# SCS.net
KiCad netlist of a schematic drawn in EAGLE
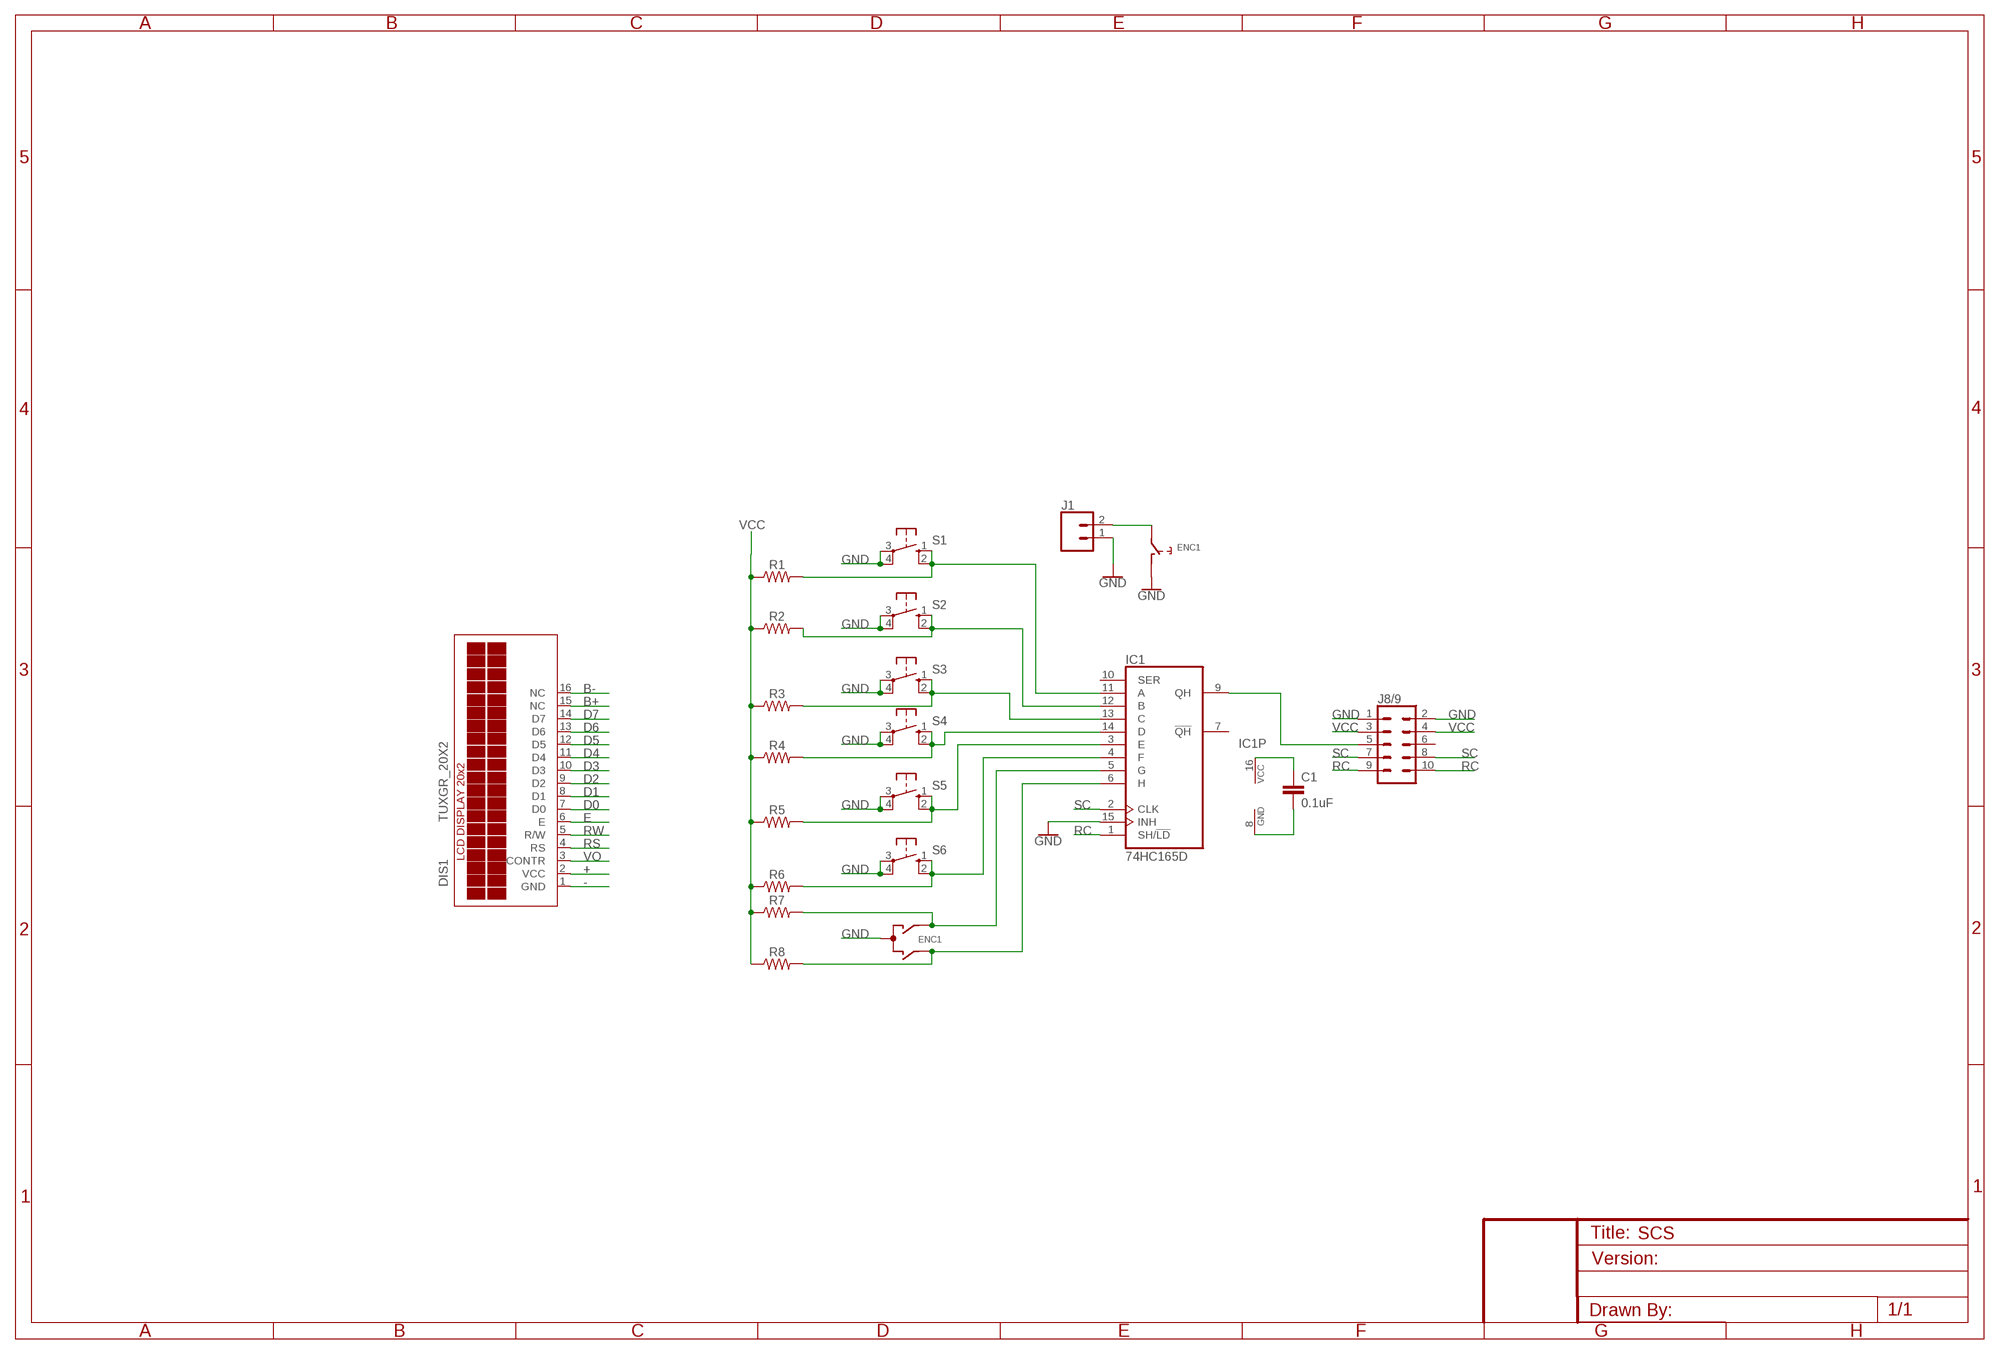
[diagram p0: schematic, sheet 1]

(export (version "E")
  (design (tool "Eeschema 10.0.6"))
  (components
    (comp (ref "C1")
      (value "0.1uF")
      (footprint "eagle-import:0603")
      (libsource (lib "eagle-import") (part "0.1UF-0603-25V-(+80/-20%)"))
    )
    (comp (ref "DIS1")
      (value "TUXGR_20X2")
      (footprint "eagle-import:TUXGR_20X2")
      (libsource (lib "eagle-import") (part "TUXGR_20X2"))
    )
    (comp (ref "ENC1")
      (value "EC12E_SW")
      (footprint "eagle-import:ALPS_EC12E_SW")
      (fields (field (name "MPN") "EC12E2424407"))
      (libsource (lib "eagle-import") (part "EC12E_SW"))
    )
    (comp (ref "IC1")
      (value "74HC165D")
      (footprint "eagle-import:SO16")
      (libsource (lib "eagle-import") (part "74165DHC"))
    )
    (comp (ref "J1")
      (value "CONN_02")
      (footprint "eagle-import:1X02")
      (libsource (lib "eagle-import") (part "CONN_02"))
    )
    (comp (ref "J8/9")
      (value "CONN_05X2SHD_LOCK")
      (footprint "eagle-import:2X5-SHROUDED_LOCK")
      (libsource (lib "eagle-import") (part "CONN_05X2SHD_LOCK"))
    )
    (comp (ref "R1")
      (value "10k")
      (footprint "eagle-import:0603")
      (libsource (lib "eagle-import") (part "10KOHM-0603-1/10W-1%"))
    )
    (comp (ref "R2")
      (value "10k")
      (footprint "eagle-import:0603")
      (libsource (lib "eagle-import") (part "10KOHM-0603-1/10W-1%"))
    )
    (comp (ref "R3")
      (value "10k")
      (footprint "eagle-import:0603")
      (libsource (lib "eagle-import") (part "10KOHM-0603-1/10W-1%"))
    )
    (comp (ref "R4")
      (value "10k")
      (footprint "eagle-import:0603")
      (libsource (lib "eagle-import") (part "10KOHM-0603-1/10W-1%"))
    )
    (comp (ref "R5")
      (value "10k")
      (footprint "eagle-import:0603")
      (libsource (lib "eagle-import") (part "10KOHM-0603-1/10W-1%"))
    )
    (comp (ref "R6")
      (value "10k")
      (footprint "eagle-import:0603")
      (libsource (lib "eagle-import") (part "10KOHM-0603-1/10W-1%"))
    )
    (comp (ref "R7")
      (value "10k")
      (footprint "eagle-import:0603")
      (libsource (lib "eagle-import") (part "10KOHM-0603-1/10W-1%"))
    )
    (comp (ref "R8")
      (value "10k")
      (footprint "eagle-import:0603")
      (libsource (lib "eagle-import") (part "10KOHM-0603-1/10W-1%"))
    )
    (comp (ref "S1")
      (value "40-XX")
      (footprint "eagle-import:B3F-40XX")
      (fields (field (name "MF") "OMRON COMPONENTS USA") (field (name "MPN") "B3F-4000"))
      (libsource (lib "eagle-import") (part "40-XX"))
    )
    (comp (ref "S2")
      (value "40-XX")
      (footprint "eagle-import:B3F-40XX")
      (fields (field (name "MF") "OMRON COMPONENTS USA") (field (name "MPN") "B3F-4000"))
      (libsource (lib "eagle-import") (part "40-XX"))
    )
    (comp (ref "S3")
      (value "40-XX")
      (footprint "eagle-import:B3F-40XX")
      (fields (field (name "MF") "OMRON COMPONENTS USA") (field (name "MPN") "B3F-4000"))
      (libsource (lib "eagle-import") (part "40-XX"))
    )
    (comp (ref "S4")
      (value "40-XX")
      (footprint "eagle-import:B3F-40XX")
      (fields (field (name "MF") "OMRON COMPONENTS USA") (field (name "MPN") "B3F-4000"))
      (libsource (lib "eagle-import") (part "40-XX"))
    )
    (comp (ref "S5")
      (value "40-XX")
      (footprint "eagle-import:B3F-40XX")
      (fields (field (name "MF") "OMRON COMPONENTS USA") (field (name "MPN") "B3F-4000"))
      (libsource (lib "eagle-import") (part "40-XX"))
    )
    (comp (ref "S6")
      (value "40-XX")
      (footprint "eagle-import:B3F-40XX")
      (fields (field (name "MF") "OMRON COMPONENTS USA") (field (name "MPN") "B3F-4000"))
      (libsource (lib "eagle-import") (part "40-XX"))
    )
  )
  (nets
    (net (code "1") (name "/+") (class "Default")
      (node (ref "DIS1") (pin "2") (pinfunction "VCC_2") (pintype "power_in"))
    )
    (net (code "2") (name "/-") (class "Default")
      (node (ref "DIS1") (pin "1") (pinfunction "GND_1") (pintype "power_in"))
    )
    (net (code "5") (name "/D0") (class "Default")
      (node (ref "DIS1") (pin "7") (pinfunction "D0_7") (pintype "input"))
    )
    (net (code "6") (name "/D1") (class "Default")
      (node (ref "DIS1") (pin "8") (pinfunction "D1_8") (pintype "input"))
    )
    (net (code "7") (name "/D2") (class "Default")
      (node (ref "DIS1") (pin "9") (pinfunction "D2_9") (pintype "input"))
    )
    (net (code "8") (name "/D3") (class "Default")
      (node (ref "DIS1") (pin "10") (pinfunction "D3_10") (pintype "input"))
    )
    (net (code "9") (name "/D4") (class "Default")
      (node (ref "DIS1") (pin "11") (pinfunction "D4_11") (pintype "input"))
    )
    (net (code "10") (name "/D5") (class "Default")
      (node (ref "DIS1") (pin "12") (pinfunction "D5_12") (pintype "input"))
    )
    (net (code "11") (name "/D6") (class "Default")
      (node (ref "DIS1") (pin "13") (pinfunction "D6_13") (pintype "input"))
    )
    (net (code "12") (name "/D7") (class "Default")
      (node (ref "DIS1") (pin "14") (pinfunction "D7_14") (pintype "input"))
    )
    (net (code "13") (name "/E") (class "Default")
      (node (ref "DIS1") (pin "6") (pinfunction "E_6") (pintype "input"))
    )
    (net (code "14") (name "/RC") (class "Default")
      (node (ref "IC1") (pin "1") (pinfunction "SH/~{LD}_1") (pintype "input"))
      (node (ref "J8/9") (pin "10") (pinfunction "10_10") (pintype "passive"))
      (node (ref "J8/9") (pin "9") (pinfunction "9_9") (pintype "passive"))
    )
    (net (code "15") (name "/RS") (class "Default")
      (node (ref "DIS1") (pin "4") (pinfunction "RS_4") (pintype "input"))
    )
    (net (code "16") (name "/RW") (class "Default")
      (node (ref "DIS1") (pin "5") (pinfunction "R/W_5") (pintype "input"))
    )
    (net (code "17") (name "/SC") (class "Default")
      (node (ref "IC1") (pin "2") (pinfunction "CLK_2") (pintype "input"))
      (node (ref "J8/9") (pin "7") (pinfunction "7_7") (pintype "passive"))
      (node (ref "J8/9") (pin "8") (pinfunction "8_8") (pintype "passive"))
    )
    (net (code "18") (name "/VCC") (class "Default")
      (node (ref "J8/9") (pin "3") (pinfunction "3_3") (pintype "passive"))
      (node (ref "J8/9") (pin "4") (pinfunction "4_4") (pintype "passive"))
      (node (ref "R1") (pin "1") (pinfunction "1_1") (pintype "passive"))
      (node (ref "R2") (pin "1") (pinfunction "1_1") (pintype "passive"))
      (node (ref "R3") (pin "1") (pinfunction "1_1") (pintype "passive"))
      (node (ref "R4") (pin "1") (pinfunction "1_1") (pintype "passive"))
      (node (ref "R5") (pin "1") (pinfunction "1_1") (pintype "passive"))
      (node (ref "R6") (pin "1") (pinfunction "1_1") (pintype "passive"))
      (node (ref "R7") (pin "1") (pinfunction "1_1") (pintype "passive"))
      (node (ref "R8") (pin "1") (pinfunction "1_1") (pintype "passive"))
    )
    (net (code "19") (name "/VO") (class "Default")
      (node (ref "DIS1") (pin "3") (pinfunction "CONTR_3") (pintype "input"))
    )
    (net (code "20") (name "GND") (class "Default")
      (node (ref "ENC1") (pin "C") (pinfunction "C_C") (pintype "passive"))
      (node (ref "ENC1") (pin "D") (pinfunction "1_D") (pintype "passive"))
      (node (ref "IC1") (pin "15") (pinfunction "INH_15") (pintype "input"))
      (node (ref "J1") (pin "1") (pinfunction "1_1") (pintype "passive"))
      (node (ref "J8/9") (pin "1") (pinfunction "1_1") (pintype "passive"))
      (node (ref "J8/9") (pin "2") (pinfunction "2_2") (pintype "passive"))
      (node (ref "S1") (pin "3") (pinfunction "P_3") (pintype "passive"))
      (node (ref "S1") (pin "4") (pinfunction "P1_4") (pintype "passive"))
      (node (ref "S2") (pin "3") (pinfunction "P_3") (pintype "passive"))
      (node (ref "S2") (pin "4") (pinfunction "P1_4") (pintype "passive"))
      (node (ref "S3") (pin "3") (pinfunction "P_3") (pintype "passive"))
      (node (ref "S3") (pin "4") (pinfunction "P1_4") (pintype "passive"))
      (node (ref "S4") (pin "3") (pinfunction "P_3") (pintype "passive"))
      (node (ref "S4") (pin "4") (pinfunction "P1_4") (pintype "passive"))
      (node (ref "S5") (pin "3") (pinfunction "P_3") (pintype "passive"))
      (node (ref "S5") (pin "4") (pinfunction "P1_4") (pintype "passive"))
      (node (ref "S6") (pin "3") (pinfunction "P_3") (pintype "passive"))
      (node (ref "S6") (pin "4") (pinfunction "P1_4") (pintype "passive"))
    )
    (net (code "21") (name "Net-(ENC1B-2)") (class "Default")
      (node (ref "ENC1") (pin "E") (pinfunction "2_E") (pintype "passive"))
      (node (ref "J1") (pin "2") (pinfunction "2_2") (pintype "passive"))
    )
    (net (code "22") (name "Net-(IC1A-A)") (class "Default")
      (node (ref "IC1") (pin "11") (pinfunction "A_11") (pintype "input"))
      (node (ref "R1") (pin "2") (pinfunction "2_2") (pintype "passive"))
      (node (ref "S1") (pin "1") (pinfunction "S_1") (pintype "passive"))
      (node (ref "S1") (pin "2") (pinfunction "S1_2") (pintype "passive"))
    )
    (net (code "23") (name "Net-(IC1A-B)") (class "Default")
      (node (ref "IC1") (pin "12") (pinfunction "B_12") (pintype "input"))
      (node (ref "R2") (pin "2") (pinfunction "2_2") (pintype "passive"))
      (node (ref "S2") (pin "1") (pinfunction "S_1") (pintype "passive"))
      (node (ref "S2") (pin "2") (pinfunction "S1_2") (pintype "passive"))
    )
    (net (code "24") (name "Net-(IC1A-C)") (class "Default")
      (node (ref "IC1") (pin "13") (pinfunction "C_13") (pintype "input"))
      (node (ref "R3") (pin "2") (pinfunction "2_2") (pintype "passive"))
      (node (ref "S3") (pin "1") (pinfunction "S_1") (pintype "passive"))
      (node (ref "S3") (pin "2") (pinfunction "S1_2") (pintype "passive"))
    )
    (net (code "25") (name "Net-(IC1A-D)") (class "Default")
      (node (ref "IC1") (pin "14") (pinfunction "D_14") (pintype "input"))
      (node (ref "R4") (pin "2") (pinfunction "2_2") (pintype "passive"))
      (node (ref "S4") (pin "1") (pinfunction "S_1") (pintype "passive"))
      (node (ref "S4") (pin "2") (pinfunction "S1_2") (pintype "passive"))
    )
    (net (code "26") (name "Net-(IC1A-E)") (class "Default")
      (node (ref "IC1") (pin "3") (pinfunction "E_3") (pintype "input"))
      (node (ref "R5") (pin "2") (pinfunction "2_2") (pintype "passive"))
      (node (ref "S5") (pin "1") (pinfunction "S_1") (pintype "passive"))
      (node (ref "S5") (pin "2") (pinfunction "S1_2") (pintype "passive"))
    )
    (net (code "27") (name "Net-(IC1A-F)") (class "Default")
      (node (ref "IC1") (pin "4") (pinfunction "F_4") (pintype "input"))
      (node (ref "R6") (pin "2") (pinfunction "2_2") (pintype "passive"))
      (node (ref "S6") (pin "1") (pinfunction "S_1") (pintype "passive"))
      (node (ref "S6") (pin "2") (pinfunction "S1_2") (pintype "passive"))
    )
    (net (code "28") (name "Net-(IC1A-G)") (class "Default")
      (node (ref "ENC1") (pin "A") (pinfunction "A_A") (pintype "passive"))
      (node (ref "IC1") (pin "5") (pinfunction "G_5") (pintype "input"))
      (node (ref "R7") (pin "2") (pinfunction "2_2") (pintype "passive"))
    )
    (net (code "29") (name "Net-(IC1A-H)") (class "Default")
      (node (ref "ENC1") (pin "B") (pinfunction "B_B") (pintype "passive"))
      (node (ref "IC1") (pin "6") (pinfunction "H_6") (pintype "input"))
      (node (ref "R8") (pin "2") (pinfunction "2_2") (pintype "passive"))
    )
    (net (code "30") (name "Net-(IC1A-QH)") (class "Default")
      (node (ref "IC1") (pin "9") (pinfunction "QH_9") (pintype "output"))
      (node (ref "J8/9") (pin "5") (pinfunction "5_5") (pintype "passive"))
    )
    (net (code "31") (name "Net-(IC1B-GND)") (class "Default")
      (node (ref "C1") (pin "2") (pinfunction "2_2") (pintype "passive"))
      (node (ref "IC1") (pin "8") (pinfunction "GND_8") (pintype "power_in"))
    )
    (net (code "32") (name "Net-(IC1B-VCC)") (class "Default")
      (node (ref "C1") (pin "1") (pinfunction "1_1") (pintype "passive"))
      (node (ref "IC1") (pin "16") (pinfunction "VCC_16") (pintype "power_in"))
    )
    (net (code "33") (name "unconnected-(DIS1-NC-Pad15)") (class "Default")
      (node (ref "DIS1") (pin "15") (pinfunction "NC_15") (pintype "no_connect"))
    )
    (net (code "34") (name "unconnected-(DIS1-NC-Pad16)") (class "Default")
      (node (ref "DIS1") (pin "16") (pinfunction "NC_16") (pintype "no_connect"))
    )
    (net (code "35") (name "unconnected-(IC1A-SER-Pad10)") (class "Default")
      (node (ref "IC1") (pin "10") (pinfunction "SER_10") (pintype "input"))
    )
    (net (code "36") (name "unconnected-(IC1A-~{QH}-Pad7)") (class "Default")
      (node (ref "IC1") (pin "7") (pinfunction "~{QH}_7") (pintype "output"))
    )
    (net (code "37") (name "unconnected-(J8/9-Pad6)") (class "Default")
      (node (ref "J8/9") (pin "6") (pinfunction "6_6") (pintype "passive"))
    )
  )
)
